# B13.net
KiCad netlist of a schematic drawn in Altium Designer
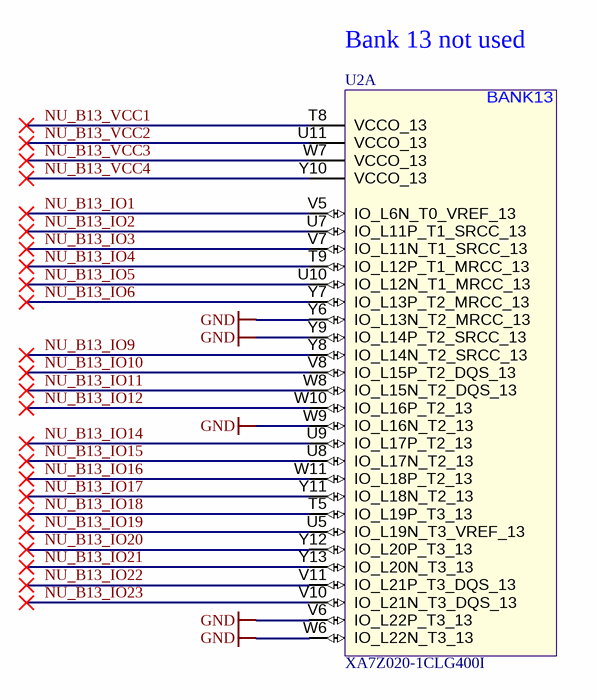
[diagram p0: B13.SchDoc]

(export (version "E")
  (design (tool "Eeschema 10.0.6"))
  (components
    (comp (ref "U2")
      (value "XA7Z020-1CLG400I")
      (footprint "BGA400C80P20X20_1700X1700X160N")
      (libsource (lib "TE") (part "XC7Z020-2CLG400C"))
    )
  )
  (nets
    (net (code "1") (name "/NU_B13_IO1") (class "Default")
      (node (ref "U2") (pin "V5") (pinfunction "IO_L6N_T0_VREF_13_V5") (pintype "bidirectional+no_connect"))
    )
    (net (code "2") (name "/NU_B13_IO2") (class "Default")
      (node (ref "U2") (pin "U7") (pinfunction "IO_L11P_T1_SRCC_13_U7") (pintype "bidirectional+no_connect"))
    )
    (net (code "3") (name "/NU_B13_IO3") (class "Default")
      (node (ref "U2") (pin "V7") (pinfunction "IO_L11N_T1_SRCC_13_V7") (pintype "bidirectional+no_connect"))
    )
    (net (code "4") (name "/NU_B13_IO4") (class "Default")
      (node (ref "U2") (pin "T9") (pinfunction "IO_L12P_T1_MRCC_13_T9") (pintype "bidirectional+no_connect"))
    )
    (net (code "5") (name "/NU_B13_IO5") (class "Default")
      (node (ref "U2") (pin "U10") (pinfunction "IO_L12N_T1_MRCC_13_U10") (pintype "bidirectional+no_connect"))
    )
    (net (code "6") (name "/NU_B13_IO6") (class "Default")
      (node (ref "U2") (pin "Y7") (pinfunction "IO_L13P_T2_MRCC_13_Y7") (pintype "bidirectional+no_connect"))
    )
    (net (code "7") (name "/NU_B13_IO9") (class "Default")
      (node (ref "U2") (pin "Y8") (pinfunction "IO_L14N_T2_SRCC_13_Y8") (pintype "bidirectional+no_connect"))
    )
    (net (code "8") (name "/NU_B13_IO10") (class "Default")
      (node (ref "U2") (pin "V8") (pinfunction "IO_L15P_T2_DQS_13_V8") (pintype "bidirectional+no_connect"))
    )
    (net (code "9") (name "/NU_B13_IO11") (class "Default")
      (node (ref "U2") (pin "W8") (pinfunction "IO_L15N_T2_DQS_13_W8") (pintype "bidirectional+no_connect"))
    )
    (net (code "10") (name "/NU_B13_IO12") (class "Default")
      (node (ref "U2") (pin "W10") (pinfunction "IO_L16P_T2_13_W10") (pintype "bidirectional+no_connect"))
    )
    (net (code "11") (name "/NU_B13_IO14") (class "Default")
      (node (ref "U2") (pin "U9") (pinfunction "IO_L17P_T2_13_U9") (pintype "bidirectional+no_connect"))
    )
    (net (code "12") (name "/NU_B13_IO15") (class "Default")
      (node (ref "U2") (pin "U8") (pinfunction "IO_L17N_T2_13_U8") (pintype "bidirectional+no_connect"))
    )
    (net (code "13") (name "/NU_B13_IO16") (class "Default")
      (node (ref "U2") (pin "W11") (pinfunction "IO_L18P_T2_13_W11") (pintype "bidirectional+no_connect"))
    )
    (net (code "14") (name "/NU_B13_IO17") (class "Default")
      (node (ref "U2") (pin "Y11") (pinfunction "IO_L18N_T2_13_Y11") (pintype "bidirectional+no_connect"))
    )
    (net (code "15") (name "/NU_B13_IO18") (class "Default")
      (node (ref "U2") (pin "T5") (pinfunction "IO_L19P_T3_13_T5") (pintype "bidirectional+no_connect"))
    )
    (net (code "16") (name "/NU_B13_IO19") (class "Default")
      (node (ref "U2") (pin "U5") (pinfunction "IO_L19N_T3_VREF_13_U5") (pintype "bidirectional+no_connect"))
    )
    (net (code "17") (name "/NU_B13_IO20") (class "Default")
      (node (ref "U2") (pin "Y12") (pinfunction "IO_L20P_T3_13_Y12") (pintype "bidirectional+no_connect"))
    )
    (net (code "18") (name "/NU_B13_IO21") (class "Default")
      (node (ref "U2") (pin "Y13") (pinfunction "IO_L20N_T3_13_Y13") (pintype "bidirectional+no_connect"))
    )
    (net (code "19") (name "/NU_B13_IO22") (class "Default")
      (node (ref "U2") (pin "V11") (pinfunction "IO_L21P_T3_DQS_13_V11") (pintype "bidirectional+no_connect"))
    )
    (net (code "20") (name "/NU_B13_IO23") (class "Default")
      (node (ref "U2") (pin "V10") (pinfunction "IO_L21N_T3_DQS_13_V10") (pintype "bidirectional+no_connect"))
    )
    (net (code "21") (name "/NU_B13_VCC1") (class "Default")
      (node (ref "U2") (pin "T8") (pinfunction "VCCO_13_T8") (pintype "power_in+no_connect"))
    )
    (net (code "22") (name "/NU_B13_VCC2") (class "Default")
      (node (ref "U2") (pin "U11") (pinfunction "VCCO_13_U11") (pintype "power_in+no_connect"))
    )
    (net (code "23") (name "/NU_B13_VCC3") (class "Default")
      (node (ref "U2") (pin "W7") (pinfunction "VCCO_13_W7") (pintype "power_in+no_connect"))
    )
    (net (code "24") (name "/NU_B13_VCC4") (class "Default")
      (node (ref "U2") (pin "Y10") (pinfunction "VCCO_13_Y10") (pintype "power_in+no_connect"))
    )
    (net (code "25") (name "GND") (class "Default")
      (node (ref "U2") (pin "V6") (pinfunction "IO_L22P_T3_13_V6") (pintype "bidirectional"))
      (node (ref "U2") (pin "W6") (pinfunction "IO_L22N_T3_13_W6") (pintype "bidirectional"))
      (node (ref "U2") (pin "W9") (pinfunction "IO_L16N_T2_13_W9") (pintype "bidirectional"))
      (node (ref "U2") (pin "Y6") (pinfunction "IO_L13N_T2_MRCC_13_Y6") (pintype "bidirectional"))
      (node (ref "U2") (pin "Y9") (pinfunction "IO_L14P_T2_SRCC_13_Y9") (pintype "bidirectional"))
    )
  )
)
